# RAMI.net
KiCad netlist of a schematic drawn in EAGLE
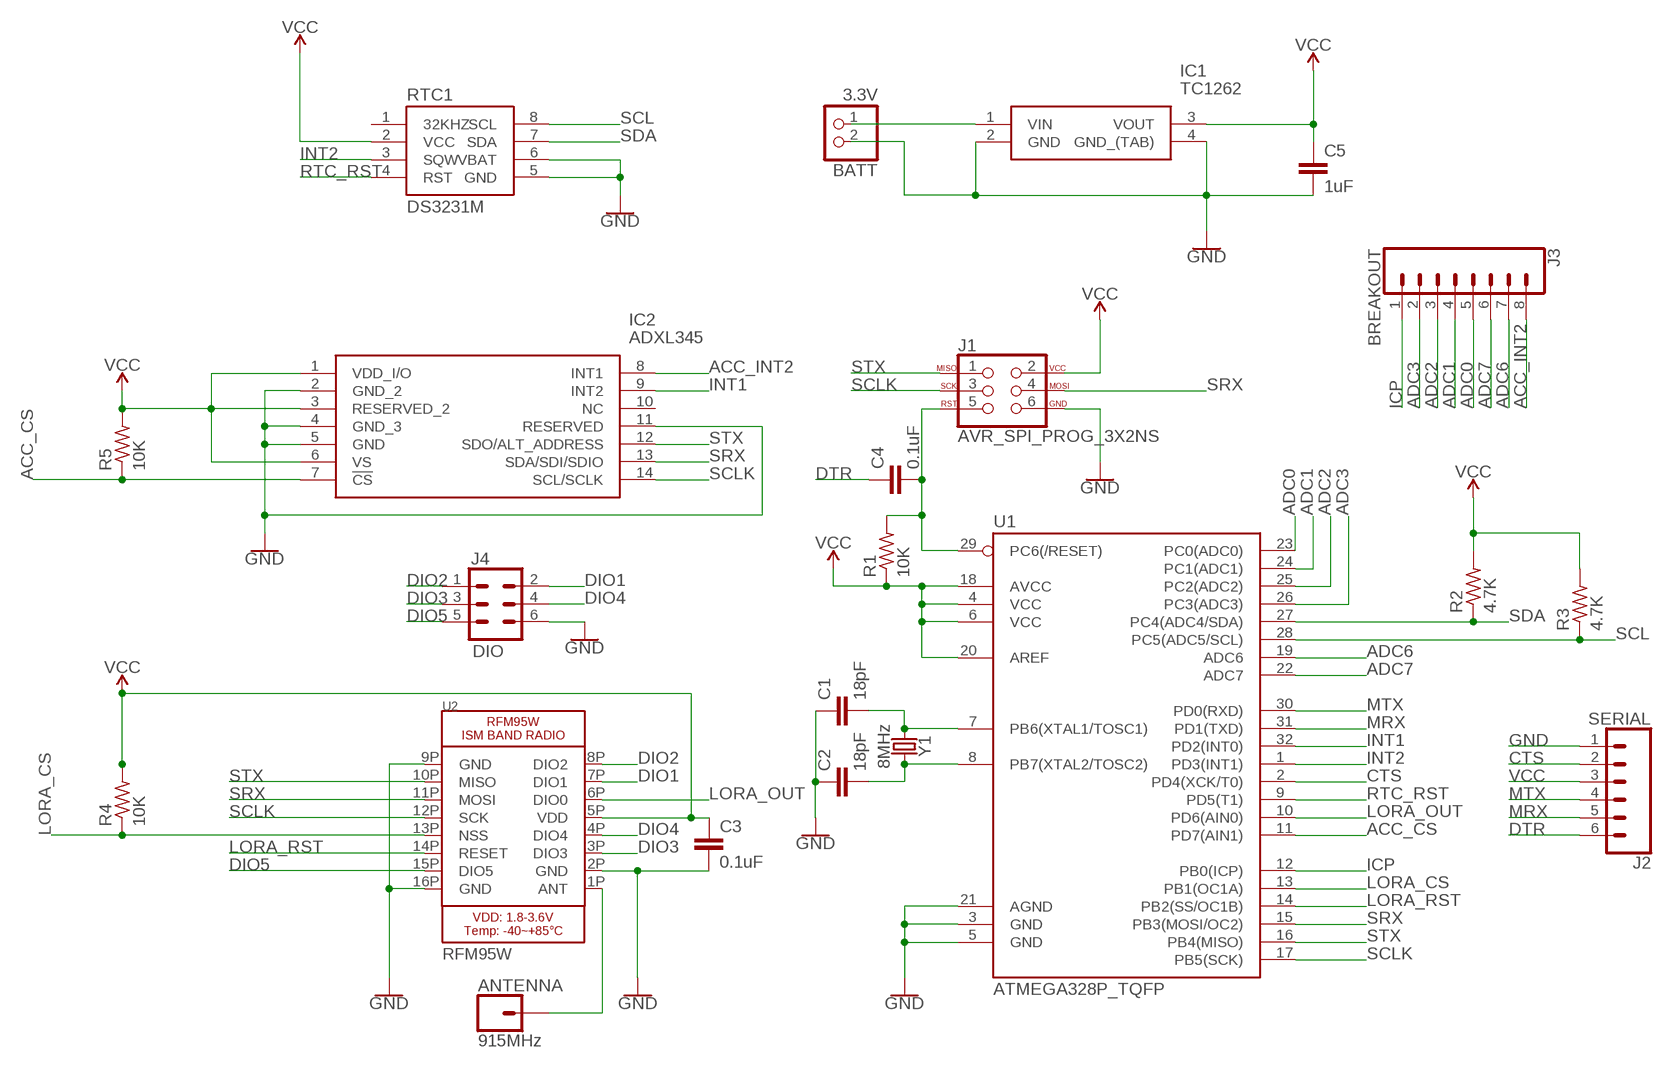
[diagram p0: schematic, sheet 1]

(export (version "E")
  (design (tool "Eeschema 10.0.6"))
  (components
    (comp (ref "ANTENNA")
      (value "915MHz")
      (footprint "eagle-import:1X01")
      (libsource (lib "eagle-import") (part "CONN_01"))
    )
    (comp (ref "BATT")
      (value "3.3V")
      (footprint "eagle-import:JST-PH-2-THM")
      (libsource (lib "eagle-import") (part "JST_2PIN-THM"))
    )
    (comp (ref "C1")
      (value "18pF")
      (footprint "eagle-import:0603")
      (libsource (lib "eagle-import") (part "18PF-0603-50V-5%"))
    )
    (comp (ref "C2")
      (value "18pF")
      (footprint "eagle-import:0603")
      (libsource (lib "eagle-import") (part "18PF-0603-50V-5%"))
    )
    (comp (ref "C3")
      (value "0.1uF")
      (footprint "eagle-import:0603")
      (libsource (lib "eagle-import") (part "0.1UF-0603-25V-5%"))
    )
    (comp (ref "C4")
      (value "0.1uF")
      (footprint "eagle-import:0603")
      (libsource (lib "eagle-import") (part "0.1UF-0603-25V-5%"))
    )
    (comp (ref "C5")
      (value "1uF")
      (footprint "eagle-import:C050-024X044")
      (libsource (lib "eagle-import") (part "C-EU050-024X044"))
    )
    (comp (ref "IC1")
      (value "TC1262")
      (footprint "eagle-import:SOT230P700X180-4N")
      (fields
        (field (name "MANUFACTURER_PART_NUMBER") "TC1262-3.3VDB")
        (field (name "MOUSER_PART_NUMBER") "579-TC1262-3.3VDB")
        (field (name "RS_PART_NUMBER") "9115732")
      )
      (libsource (lib "eagle-import") (part "TC1262-3.3VDB"))
    )
    (comp (ref "IC2")
      (value "ADXL345")
      (footprint "eagle-import:LGA14R80P3X6_300X500X100")
      (fields
        (field (name "MANUFACTURER_PART_NUMBER") "ADXL345BCCZ")
        (field (name "MOUSER_PART_NUMBER") "584-ADXL345BCCZ")
        (field (name "RS_PART_NUMBER") "7098439P")
      )
      (libsource (lib "eagle-import") (part "ADXL345BCCZ"))
    )
    (comp (ref "J1")
      (value "AVR_SPI_PROG_3X2NS")
      (footprint "eagle-import:2X3-NS")
      (libsource (lib "eagle-import") (part "AVR_SPI_PROG_3X2NS"))
    )
    (comp (ref "J2")
      (value "SERIAL")
      (footprint "eagle-import:1X06_LOCK")
      (libsource (lib "eagle-import") (part "CONN_06LOCK"))
    )
    (comp (ref "J3")
      (value "BREAKOUT")
      (footprint "eagle-import:1X08")
      (libsource (lib "eagle-import") (part "CONN_08{dblquote}"))
    )
    (comp (ref "J4")
      (value "DIO")
      (footprint "eagle-import:2X3-NS")
      (libsource (lib "eagle-import") (part "CONN_03X2NO_SILK"))
    )
    (comp (ref "R1")
      (value "10K")
      (footprint "eagle-import:R0603")
      (libsource (lib "eagle-import") (part "R-US_R0603"))
    )
    (comp (ref "R2")
      (value "4.7K")
      (footprint "eagle-import:R0603")
      (libsource (lib "eagle-import") (part "R-US_R0603"))
    )
    (comp (ref "R3")
      (value "4.7K")
      (footprint "eagle-import:R0603")
      (libsource (lib "eagle-import") (part "R-US_R0603"))
    )
    (comp (ref "R4")
      (value "10K")
      (footprint "eagle-import:R0603")
      (libsource (lib "eagle-import") (part "R-US_R0603"))
    )
    (comp (ref "R5")
      (value "10K")
      (footprint "eagle-import:R0603")
      (libsource (lib "eagle-import") (part "R-US_R0603"))
    )
    (comp (ref "RTC1")
      (value "DS3231M")
      (footprint "eagle-import:SO08")
      (libsource (lib "eagle-import") (part "DS3231M"))
    )
    (comp (ref "U1")
      (value "ATMEGA328P_TQFP")
      (footprint "eagle-import:TQFP32-08")
      (libsource (lib "eagle-import") (part "ATMEGA328P_TQFP"))
    )
    (comp (ref "U2")
      (value "RFM95W")
      (footprint "eagle-import:RFM95W_SMT")
      (libsource (lib "eagle-import") (part "RFM95W_SMT"))
    )
    (comp (ref "Y1")
      (value "8MHz")
      (footprint "eagle-import:HC49US")
      (libsource (lib "eagle-import") (part "CRYSTALPTH-HC49US"))
    )
  )
  (nets
    (net (code "1") (name "/ACC_CS") (class "Default")
      (node (ref "IC2") (pin "7") (pinfunction "~{CS}_7") (pintype "bidirectional"))
      (node (ref "R5") (pin "1") (pinfunction "1_1") (pintype "passive"))
      (node (ref "U1") (pin "11") (pinfunction "PD7(AIN1)_11") (pintype "bidirectional"))
    )
    (net (code "2") (name "/ACC_INT2") (class "Default")
      (node (ref "IC2") (pin "8") (pinfunction "INT1_8") (pintype "bidirectional"))
      (node (ref "J3") (pin "8") (pinfunction "8_8") (pintype "passive"))
    )
    (net (code "3") (name "/ADC0") (class "Default")
      (node (ref "J3") (pin "5") (pinfunction "5_5") (pintype "passive"))
      (node (ref "U1") (pin "23") (pinfunction "PC0(ADC0)_23") (pintype "bidirectional"))
    )
    (net (code "4") (name "/ADC1") (class "Default")
      (node (ref "J3") (pin "4") (pinfunction "4_4") (pintype "passive"))
      (node (ref "U1") (pin "24") (pinfunction "PC1(ADC1)_24") (pintype "bidirectional"))
    )
    (net (code "5") (name "/ADC2") (class "Default")
      (node (ref "J3") (pin "3") (pinfunction "3_3") (pintype "passive"))
      (node (ref "U1") (pin "25") (pinfunction "PC2(ADC2)_25") (pintype "bidirectional"))
    )
    (net (code "6") (name "/ADC3") (class "Default")
      (node (ref "J3") (pin "2") (pinfunction "2_2") (pintype "passive"))
      (node (ref "U1") (pin "26") (pinfunction "PC3(ADC3)_26") (pintype "bidirectional"))
    )
    (net (code "7") (name "/ADC6") (class "Default")
      (node (ref "J3") (pin "7") (pinfunction "7_7") (pintype "passive"))
      (node (ref "U1") (pin "19") (pinfunction "ADC6_19") (pintype "bidirectional"))
    )
    (net (code "8") (name "/ADC7") (class "Default")
      (node (ref "J3") (pin "6") (pinfunction "6_6") (pintype "passive"))
      (node (ref "U1") (pin "22") (pinfunction "ADC7_22") (pintype "bidirectional"))
    )
    (net (code "9") (name "/CTS") (class "Default")
      (node (ref "J2") (pin "2") (pinfunction "2_2") (pintype "passive"))
      (node (ref "U1") (pin "2") (pinfunction "PD4(XCK/T0)_2") (pintype "bidirectional"))
    )
    (net (code "10") (name "/DIO1") (class "Default")
      (node (ref "J4") (pin "2") (pinfunction "2_2") (pintype "bidirectional"))
      (node (ref "U2") (pin "7P") (pinfunction "DIO1_7P") (pintype "bidirectional"))
    )
    (net (code "11") (name "/DIO2") (class "Default")
      (node (ref "J4") (pin "1") (pinfunction "1_1") (pintype "bidirectional"))
      (node (ref "U2") (pin "8P") (pinfunction "DIO2_8P") (pintype "bidirectional"))
    )
    (net (code "12") (name "/DIO3") (class "Default")
      (node (ref "J4") (pin "3") (pinfunction "3_3") (pintype "bidirectional"))
      (node (ref "U2") (pin "3P") (pinfunction "DIO3_3P") (pintype "bidirectional"))
    )
    (net (code "13") (name "/DIO4") (class "Default")
      (node (ref "J4") (pin "4") (pinfunction "4_4") (pintype "bidirectional"))
      (node (ref "U2") (pin "4P") (pinfunction "DIO4_4P") (pintype "bidirectional"))
    )
    (net (code "14") (name "/DIO5") (class "Default")
      (node (ref "J4") (pin "5") (pinfunction "5_5") (pintype "bidirectional"))
      (node (ref "U2") (pin "15P") (pinfunction "DIO5_15P") (pintype "bidirectional"))
    )
    (net (code "15") (name "/DTR") (class "Default")
      (node (ref "C4") (pin "1") (pinfunction "1_1") (pintype "passive"))
      (node (ref "J2") (pin "6") (pinfunction "6_6") (pintype "passive"))
    )
    (net (code "16") (name "/ICP") (class "Default")
      (node (ref "J3") (pin "1") (pinfunction "1_1") (pintype "passive"))
      (node (ref "U1") (pin "12") (pinfunction "PB0(ICP)_12") (pintype "bidirectional"))
    )
    (net (code "17") (name "/INT1") (class "Default")
      (node (ref "IC2") (pin "9") (pinfunction "INT2_9") (pintype "bidirectional"))
      (node (ref "U1") (pin "32") (pinfunction "PD2(INT0)_32") (pintype "bidirectional"))
    )
    (net (code "18") (name "/INT2") (class "Default")
      (node (ref "RTC1") (pin "3") (pinfunction "SQW_3") (pintype "output"))
      (node (ref "U1") (pin "1") (pinfunction "PD3(INT1)_1") (pintype "bidirectional"))
    )
    (net (code "19") (name "/LORA_CS") (class "Default")
      (node (ref "R4") (pin "1") (pinfunction "1_1") (pintype "passive"))
      (node (ref "U1") (pin "13") (pinfunction "PB1(OC1A)_13") (pintype "bidirectional"))
      (node (ref "U2") (pin "13P") (pinfunction "NSS_13P") (pintype "input"))
    )
    (net (code "20") (name "/LORA_OUT") (class "Default")
      (node (ref "U1") (pin "10") (pinfunction "PD6(AIN0)_10") (pintype "bidirectional"))
      (node (ref "U2") (pin "6P") (pinfunction "DIO0_6P") (pintype "bidirectional"))
    )
    (net (code "21") (name "/LORA_RST") (class "Default")
      (node (ref "U1") (pin "14") (pinfunction "PB2(SS/OC1B)_14") (pintype "bidirectional"))
      (node (ref "U2") (pin "14P") (pinfunction "RESET_14P") (pintype "input"))
    )
    (net (code "22") (name "/MRX") (class "Default")
      (node (ref "J2") (pin "5") (pinfunction "5_5") (pintype "passive"))
      (node (ref "U1") (pin "31") (pinfunction "PD1(TXD)_31") (pintype "bidirectional"))
    )
    (net (code "23") (name "/MTX") (class "Default")
      (node (ref "J2") (pin "4") (pinfunction "4_4") (pintype "passive"))
      (node (ref "U1") (pin "30") (pinfunction "PD0(RXD)_30") (pintype "bidirectional"))
    )
    (net (code "24") (name "/RTC_RST") (class "Default")
      (node (ref "RTC1") (pin "4") (pinfunction "RST_4") (pintype "bidirectional"))
      (node (ref "U1") (pin "9") (pinfunction "PD5(T1)_9") (pintype "bidirectional"))
    )
    (net (code "25") (name "/SCL") (class "Default")
      (node (ref "R3") (pin "1") (pinfunction "1_1") (pintype "passive"))
      (node (ref "RTC1") (pin "8") (pinfunction "SCL_8") (pintype "bidirectional"))
      (node (ref "U1") (pin "28") (pinfunction "PC5(ADC5/SCL)_28") (pintype "bidirectional"))
    )
    (net (code "26") (name "/SCLK") (class "Default")
      (node (ref "IC2") (pin "14") (pinfunction "SCL/SCLK_14") (pintype "bidirectional"))
      (node (ref "J1") (pin "3") (pinfunction "3_3") (pintype "passive"))
      (node (ref "U1") (pin "17") (pinfunction "PB5(SCK)_17") (pintype "bidirectional"))
      (node (ref "U2") (pin "12P") (pinfunction "SCK_12P") (pintype "input"))
    )
    (net (code "27") (name "/SDA") (class "Default")
      (node (ref "R2") (pin "1") (pinfunction "1_1") (pintype "passive"))
      (node (ref "RTC1") (pin "7") (pinfunction "SDA_7") (pintype "bidirectional"))
      (node (ref "U1") (pin "27") (pinfunction "PC4(ADC4/SDA)_27") (pintype "bidirectional"))
    )
    (net (code "28") (name "/SRX") (class "Default")
      (node (ref "IC2") (pin "13") (pinfunction "SDA/SDI/SDIO_13") (pintype "bidirectional"))
      (node (ref "J1") (pin "4") (pinfunction "4_4") (pintype "passive"))
      (node (ref "U1") (pin "15") (pinfunction "PB3(MOSI/OC2)_15") (pintype "bidirectional"))
      (node (ref "U2") (pin "11P") (pinfunction "MOSI_11P") (pintype "input"))
    )
    (net (code "29") (name "/STX") (class "Default")
      (node (ref "IC2") (pin "12") (pinfunction "SDO/ALT_ADDRESS_12") (pintype "bidirectional"))
      (node (ref "J1") (pin "1") (pinfunction "1_1") (pintype "passive"))
      (node (ref "U1") (pin "16") (pinfunction "PB4(MISO)_16") (pintype "bidirectional"))
      (node (ref "U2") (pin "10P") (pinfunction "MISO_10P") (pintype "output"))
    )
    (net (code "30") (name "GND") (class "Default")
      (node (ref "BATT") (pin "2") (pinfunction "1_2") (pintype "passive"))
      (node (ref "C1") (pin "1") (pinfunction "1_1") (pintype "passive"))
      (node (ref "C2") (pin "1") (pinfunction "1_1") (pintype "passive"))
      (node (ref "C3") (pin "2") (pinfunction "2_2") (pintype "passive"))
      (node (ref "C5") (pin "2") (pinfunction "2_2") (pintype "passive"))
      (node (ref "IC1") (pin "2") (pinfunction "GND_2") (pintype "power_in"))
      (node (ref "IC1") (pin "4") (pinfunction "GND_(TAB)_4") (pintype "power_in"))
      (node (ref "IC2") (pin "11") (pinfunction "RESERVED_11") (pintype "bidirectional"))
      (node (ref "IC2") (pin "2") (pinfunction "GND_2_2") (pintype "bidirectional"))
      (node (ref "IC2") (pin "4") (pinfunction "GND_3_4") (pintype "bidirectional"))
      (node (ref "IC2") (pin "5") (pinfunction "GND_5") (pintype "bidirectional"))
      (node (ref "J1") (pin "6") (pinfunction "6_6") (pintype "passive"))
      (node (ref "J2") (pin "1") (pinfunction "1_1") (pintype "passive"))
      (node (ref "J4") (pin "6") (pinfunction "6_6") (pintype "bidirectional"))
      (node (ref "RTC1") (pin "5") (pinfunction "GND_5") (pintype "power_in"))
      (node (ref "RTC1") (pin "6") (pinfunction "VBAT_6") (pintype "power_in"))
      (node (ref "U1") (pin "21") (pinfunction "AGND_21") (pintype "bidirectional"))
      (node (ref "U1") (pin "3") (pinfunction "GND_3") (pintype "bidirectional"))
      (node (ref "U1") (pin "5") (pinfunction "GND_5") (pintype "bidirectional"))
      (node (ref "U2") (pin "16P") (pinfunction "GND_16P") (pintype "power_in"))
      (node (ref "U2") (pin "2P") (pinfunction "GND_2P") (pintype "power_in"))
      (node (ref "U2") (pin "9P") (pinfunction "GND_9P") (pintype "power_in"))
    )
    (net (code "31") (name "Net-(BATT-2)") (class "Default")
      (node (ref "BATT") (pin "1") (pinfunction "2_1") (pintype "passive"))
      (node (ref "IC1") (pin "1") (pinfunction "VIN_1") (pintype "input"))
    )
    (net (code "32") (name "Net-(U1-PB6(XTAL1{slash}TOSC1))") (class "Default")
      (node (ref "C1") (pin "2") (pinfunction "2_2") (pintype "passive"))
      (node (ref "U1") (pin "7") (pinfunction "PB6(XTAL1/TOSC1)_7") (pintype "bidirectional"))
      (node (ref "Y1") (pin "1") (pinfunction "1_1") (pintype "passive"))
    )
    (net (code "33") (name "Net-(U1-PB7(XTAL2{slash}TOSC2))") (class "Default")
      (node (ref "C2") (pin "2") (pinfunction "2_2") (pintype "passive"))
      (node (ref "U1") (pin "8") (pinfunction "PB7(XTAL2/TOSC2)_8") (pintype "bidirectional"))
      (node (ref "Y1") (pin "2") (pinfunction "2_2") (pintype "passive"))
    )
    (net (code "34") (name "Net-(U1-PC6({slash}RESET))") (class "Default")
      (node (ref "C4") (pin "2") (pinfunction "2_2") (pintype "passive"))
      (node (ref "J1") (pin "5") (pinfunction "5_5") (pintype "passive"))
      (node (ref "R1") (pin "2") (pinfunction "2_2") (pintype "passive"))
      (node (ref "U1") (pin "29") (pinfunction "PC6(/RESET)_29") (pintype "bidirectional"))
    )
    (net (code "35") (name "Net-(U2-ANT)") (class "Default")
      (node (ref "ANTENNA") (pin "1") (pinfunction "1_1") (pintype "passive"))
      (node (ref "U2") (pin "1P") (pinfunction "ANT_1P") (pintype "bidirectional"))
    )
    (net (code "36") (name "VCC") (class "Default")
      (node (ref "C3") (pin "1") (pinfunction "1_1") (pintype "passive"))
      (node (ref "C5") (pin "1") (pinfunction "1_1") (pintype "passive"))
      (node (ref "IC1") (pin "3") (pinfunction "VOUT_3") (pintype "output"))
      (node (ref "IC2") (pin "1") (pinfunction "VDD_I/O_1") (pintype "bidirectional"))
      (node (ref "IC2") (pin "3") (pinfunction "RESERVED_2_3") (pintype "bidirectional"))
      (node (ref "IC2") (pin "6") (pinfunction "VS_6") (pintype "bidirectional"))
      (node (ref "J1") (pin "2") (pinfunction "2_2") (pintype "passive"))
      (node (ref "J2") (pin "3") (pinfunction "3_3") (pintype "passive"))
      (node (ref "R1") (pin "1") (pinfunction "1_1") (pintype "passive"))
      (node (ref "R2") (pin "2") (pinfunction "2_2") (pintype "passive"))
      (node (ref "R3") (pin "2") (pinfunction "2_2") (pintype "passive"))
      (node (ref "R4") (pin "2") (pinfunction "2_2") (pintype "passive"))
      (node (ref "R5") (pin "2") (pinfunction "2_2") (pintype "passive"))
      (node (ref "RTC1") (pin "2") (pinfunction "VCC_2") (pintype "power_in"))
      (node (ref "U1") (pin "18") (pinfunction "AVCC_18") (pintype "bidirectional"))
      (node (ref "U1") (pin "20") (pinfunction "AREF_20") (pintype "bidirectional"))
      (node (ref "U1") (pin "4") (pinfunction "VCC_4") (pintype "bidirectional"))
      (node (ref "U1") (pin "6") (pinfunction "VCC_6") (pintype "bidirectional"))
      (node (ref "U2") (pin "5P") (pinfunction "VDD_5P") (pintype "power_in"))
    )
    (net (code "37") (name "unconnected-(IC2-NC-Pad10)") (class "Default")
      (node (ref "IC2") (pin "10") (pinfunction "NC_10") (pintype "no_connect"))
    )
    (net (code "38") (name "unconnected-(RTC1-32KHZ-Pad1)") (class "Default")
      (node (ref "RTC1") (pin "1") (pinfunction "32KHZ_1") (pintype "output"))
    )
  )
)
